# jst_splitter.net
KiCad netlist of a schematic drawn in EAGLE
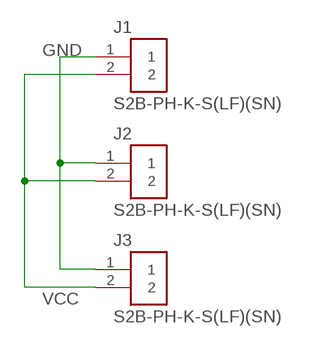
[diagram p0: schematic, sheet 1]

(export (version "E")
  (design (tool "Eeschema 10.0.6"))
  (components
    (comp (ref "J1")
      (value "S2B-PH-K-S(LF)(SN)")
      (footprint "eagle-import:S2B-PH-K-S(LF)(SN)")
      (fields
        (field (name "DIGI_KEY_PART_NUMBER") "455-1719-ND")
        (field (name "MANUFACTURER") "JST Sales America Inc.")
        (field (name "CREATED_BY") "PCBLayout.com")
      )
      (libsource (lib "eagle-import") (part "S2B-PH-K-S(LF)(SN)"))
    )
    (comp (ref "J2")
      (value "S2B-PH-K-S(LF)(SN)")
      (footprint "eagle-import:S2B-PH-K-S(LF)(SN)")
      (fields
        (field (name "DIGI_KEY_PART_NUMBER") "455-1719-ND")
        (field (name "MANUFACTURER") "JST Sales America Inc.")
        (field (name "CREATED_BY") "PCBLayout.com")
      )
      (libsource (lib "eagle-import") (part "S2B-PH-K-S(LF)(SN)"))
    )
    (comp (ref "J3")
      (value "S2B-PH-K-S(LF)(SN)")
      (footprint "eagle-import:S2B-PH-K-S(LF)(SN)")
      (fields
        (field (name "DIGI_KEY_PART_NUMBER") "455-1719-ND")
        (field (name "MANUFACTURER") "JST Sales America Inc.")
        (field (name "CREATED_BY") "PCBLayout.com")
      )
      (libsource (lib "eagle-import") (part "S2B-PH-K-S(LF)(SN)"))
    )
  )
  (nets
    (net (code "1") (name "/GND") (class "Default")
      (node (ref "J1") (pin "1") (pinfunction "1_1") (pintype "passive"))
      (node (ref "J2") (pin "1") (pinfunction "1_1") (pintype "passive"))
      (node (ref "J3") (pin "1") (pinfunction "1_1") (pintype "passive"))
    )
    (net (code "2") (name "/VCC") (class "Default")
      (node (ref "J1") (pin "2") (pinfunction "2_2") (pintype "passive"))
      (node (ref "J2") (pin "2") (pinfunction "2_2") (pintype "passive"))
      (node (ref "J3") (pin "2") (pinfunction "2_2") (pintype "passive"))
    )
  )
)
